# dm_in.net
KiCad netlist of a schematic drawn in EAGLE
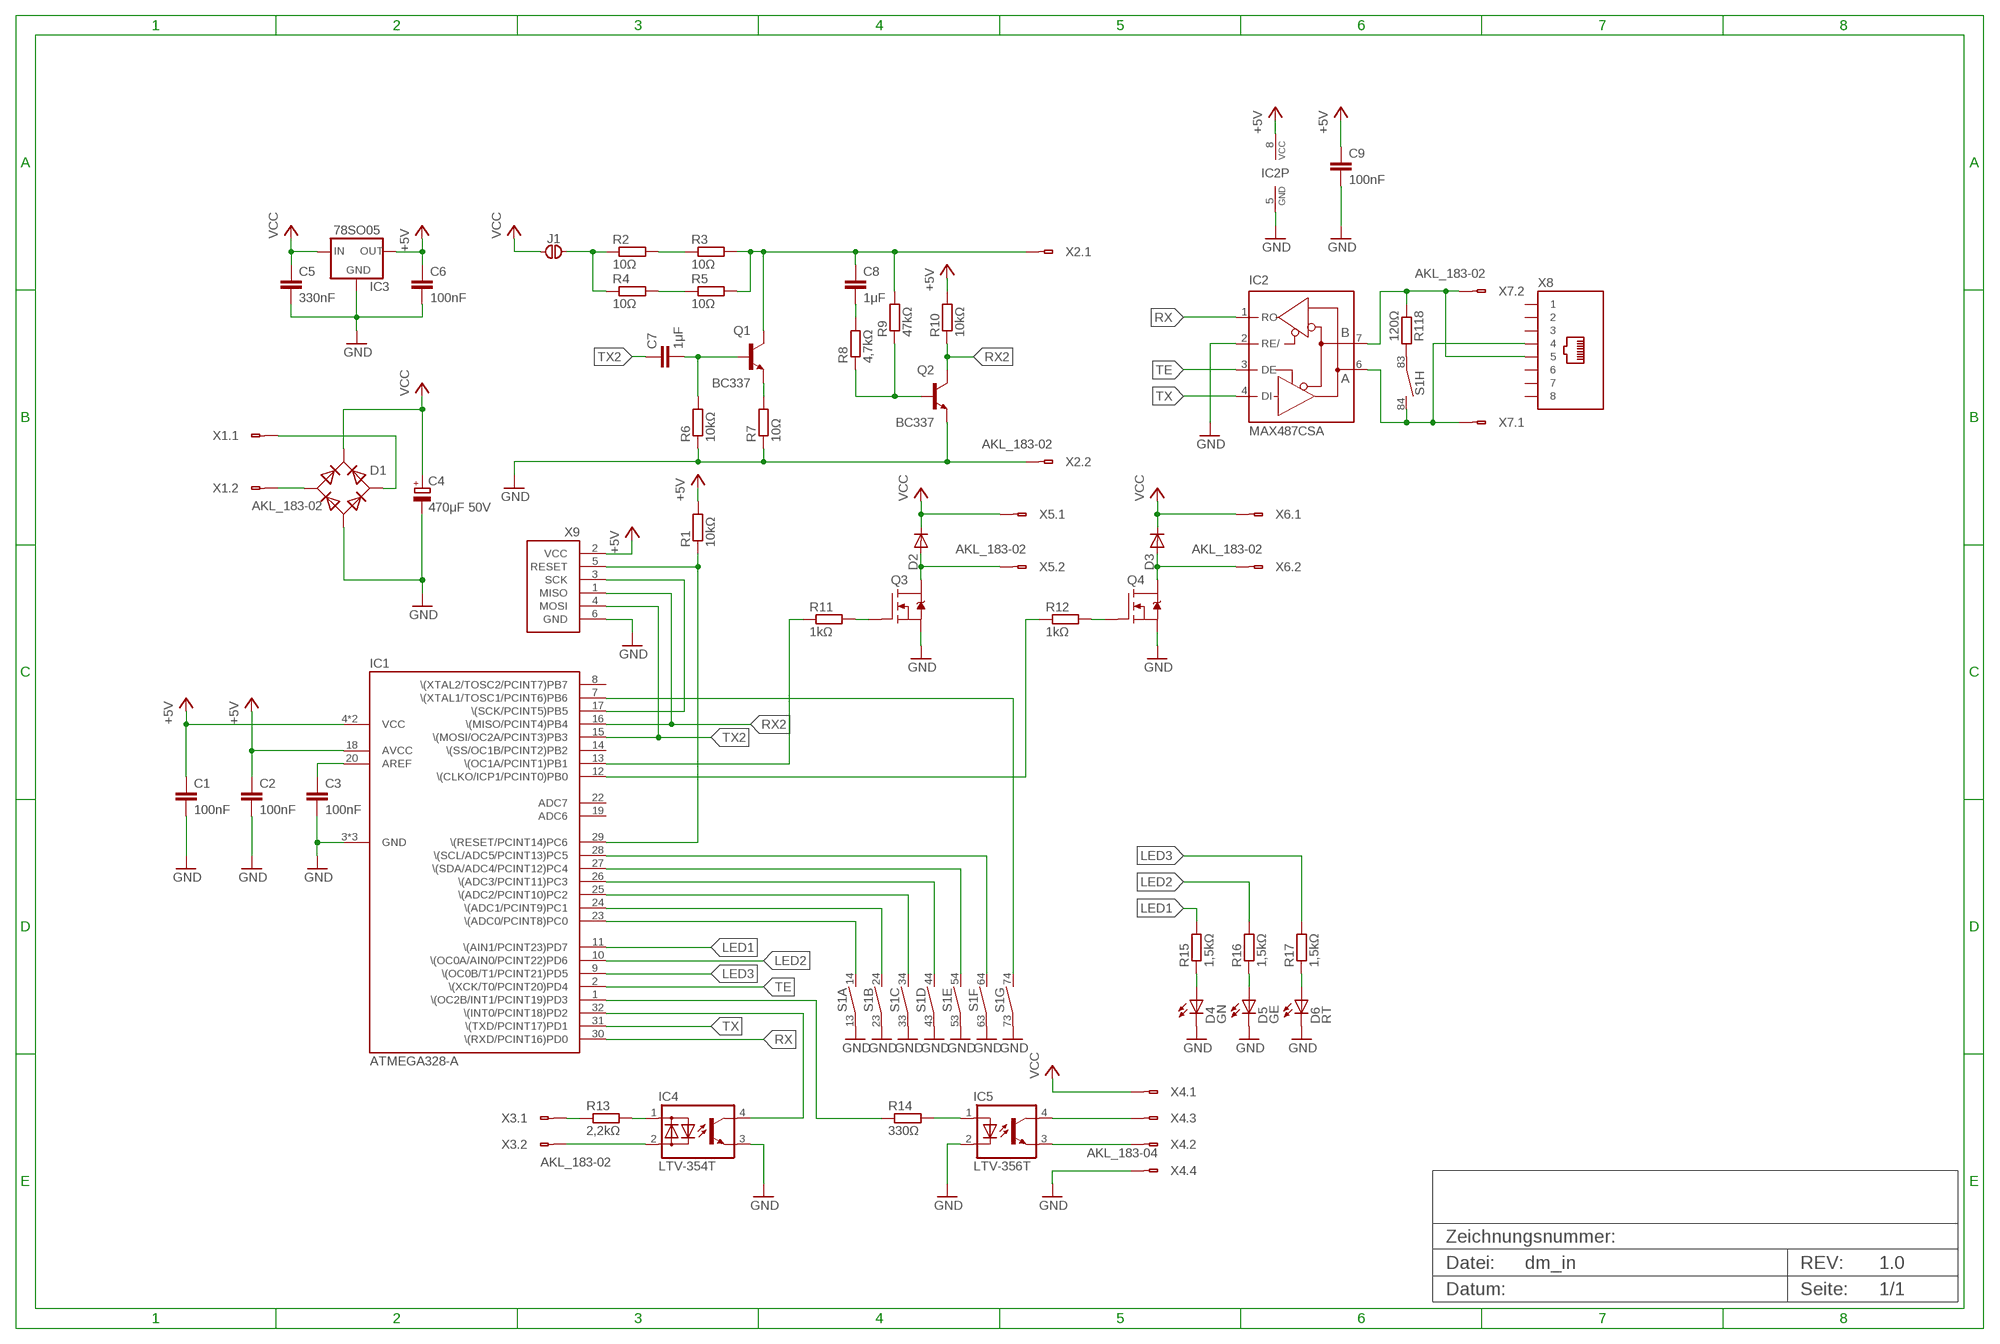
[diagram p0: schematic, sheet 1]

(export (version "E")
  (design (tool "Eeschema 10.0.6"))
  (components
    (comp (ref "C1")
      (value "100nF")
      (footprint "eagle-import:CHIP_0603")
      (libsource (lib "eagle-import") (part "C_0603"))
    )
    (comp (ref "C2")
      (value "100nF")
      (footprint "eagle-import:CHIP_0603")
      (libsource (lib "eagle-import") (part "C_0603"))
    )
    (comp (ref "C3")
      (value "100nF")
      (footprint "eagle-import:CHIP_0603")
      (libsource (lib "eagle-import") (part "C_0603"))
    )
    (comp (ref "C4")
      (value "470μF 50V")
      (footprint "eagle-import:E5-13")
      (libsource (lib "eagle-import") (part "C_EL_E5-13"))
    )
    (comp (ref "C5")
      (value "330nF")
      (footprint "eagle-import:CHIP_0805")
      (libsource (lib "eagle-import") (part "C_0805"))
    )
    (comp (ref "C6")
      (value "100nF")
      (footprint "eagle-import:CHIP_0805")
      (libsource (lib "eagle-import") (part "C_0805"))
    )
    (comp (ref "C7")
      (value "1μF")
      (footprint "eagle-import:CHIP_1206")
      (libsource (lib "eagle-import") (part "C_1206"))
    )
    (comp (ref "C8")
      (value "1μF")
      (footprint "eagle-import:CHIP_1206")
      (libsource (lib "eagle-import") (part "C_1206"))
    )
    (comp (ref "C9")
      (value "100nF")
      (footprint "eagle-import:CHIP_0603")
      (libsource (lib "eagle-import") (part "C_0603"))
    )
    (comp (ref "D1")
      (value "GLEICHRICHTER-SDIP")
      (footprint "eagle-import:SDIP04_508")
      (libsource (lib "eagle-import") (part "GLEICHRICHTER-SDIP"))
    )
    (comp (ref "D2")
      (value "DIODE-SOD123")
      (footprint "eagle-import:SOD123")
      (libsource (lib "eagle-import") (part "DIODE-SOD123"))
    )
    (comp (ref "D3")
      (value "DIODE-SOD123")
      (footprint "eagle-import:SOD123")
      (libsource (lib "eagle-import") (part "DIODE-SOD123"))
    )
    (comp (ref "D4")
      (value "GN")
      (footprint "eagle-import:CHIP_0805")
      (libsource (lib "eagle-import") (part "LED_0805"))
    )
    (comp (ref "D5")
      (value "GE")
      (footprint "eagle-import:CHIP_0805")
      (libsource (lib "eagle-import") (part "LED_0805"))
    )
    (comp (ref "D6")
      (value "RT")
      (footprint "eagle-import:CHIP_0805")
      (libsource (lib "eagle-import") (part "LED_0805"))
    )
    (comp (ref "IC1")
      (value "ATMEGA328-A")
      (footprint "eagle-import:QFP32_08")
      (libsource (lib "eagle-import") (part "ATMEGA328-A"))
    )
    (comp (ref "IC2")
      (value "MAX487CSA")
      (footprint "eagle-import:SOP08_127")
      (libsource (lib "eagle-import") (part "MAX48CSA7"))
    )
    (comp (ref "IC3")
      (value "78SO05")
      (footprint "eagle-import:SOP08_127")
      (libsource (lib "eagle-import") (part "78?SO05"))
    )
    (comp (ref "IC4")
      (value "LTV-354T")
      (footprint "eagle-import:SOP04_254")
      (libsource (lib "eagle-import") (part "LTV-354T"))
    )
    (comp (ref "IC5")
      (value "LTV-356T")
      (footprint "eagle-import:SOP04_254")
      (libsource (lib "eagle-import") (part "LTV-356T"))
    )
    (comp (ref "J1")
      (value "JUMPER")
      (footprint "eagle-import:JUMPER2")
      (libsource (lib "eagle-import") (part "JUMPER"))
    )
    (comp (ref "Q1")
      (value "BC337")
      (footprint "eagle-import:SOT23")
      (libsource (lib "eagle-import") (part "NPN-SOT23-BEC"))
    )
    (comp (ref "Q2")
      (value "BC337")
      (footprint "eagle-import:SOT23")
      (libsource (lib "eagle-import") (part "NPN-SOT23-BEC"))
    )
    (comp (ref "Q3")
      (value "N-MOS-SOT23-GSD")
      (footprint "eagle-import:SOT23")
      (libsource (lib "eagle-import") (part "N-MOS-SOT23-GSD"))
    )
    (comp (ref "Q4")
      (value "N-MOS-SOT23-GSD")
      (footprint "eagle-import:SOT23")
      (libsource (lib "eagle-import") (part "N-MOS-SOT23-GSD"))
    )
    (comp (ref "R1")
      (value "10kΩ")
      (footprint "eagle-import:CHIP_0603")
      (libsource (lib "eagle-import") (part "R_0603"))
    )
    (comp (ref "R2")
      (value "10Ω")
      (footprint "eagle-import:CHIP_1206")
      (libsource (lib "eagle-import") (part "R_1206"))
    )
    (comp (ref "R3")
      (value "10Ω")
      (footprint "eagle-import:CHIP_1206")
      (libsource (lib "eagle-import") (part "R_1206"))
    )
    (comp (ref "R4")
      (value "10Ω")
      (footprint "eagle-import:CHIP_1206")
      (libsource (lib "eagle-import") (part "R_1206"))
    )
    (comp (ref "R5")
      (value "10Ω")
      (footprint "eagle-import:CHIP_1206")
      (libsource (lib "eagle-import") (part "R_1206"))
    )
    (comp (ref "R6")
      (value "10kΩ")
      (footprint "eagle-import:CHIP_0603")
      (libsource (lib "eagle-import") (part "R_0603"))
    )
    (comp (ref "R7")
      (value "10Ω")
      (footprint "eagle-import:CHIP_1206")
      (libsource (lib "eagle-import") (part "R_1206"))
    )
    (comp (ref "R8")
      (value "4,7kΩ")
      (footprint "eagle-import:CHIP_0603")
      (libsource (lib "eagle-import") (part "R_0603"))
    )
    (comp (ref "R9")
      (value "47kΩ")
      (footprint "eagle-import:CHIP_0603")
      (libsource (lib "eagle-import") (part "R_0603"))
    )
    (comp (ref "R10")
      (value "10kΩ")
      (footprint "eagle-import:CHIP_0603")
      (libsource (lib "eagle-import") (part "R_0603"))
    )
    (comp (ref "R11")
      (value "1kΩ")
      (footprint "eagle-import:CHIP_0603")
      (libsource (lib "eagle-import") (part "R_0603"))
    )
    (comp (ref "R12")
      (value "1kΩ")
      (footprint "eagle-import:CHIP_0603")
      (libsource (lib "eagle-import") (part "R_0603"))
    )
    (comp (ref "R13")
      (value "2,2kΩ")
      (footprint "eagle-import:CHIP_0603")
      (libsource (lib "eagle-import") (part "R_0603"))
    )
    (comp (ref "R14")
      (value "330Ω")
      (footprint "eagle-import:CHIP_0603")
      (libsource (lib "eagle-import") (part "R_0603"))
    )
    (comp (ref "R15")
      (value "1,5kΩ")
      (footprint "eagle-import:CHIP_0603")
      (libsource (lib "eagle-import") (part "R_0603"))
    )
    (comp (ref "R16")
      (value "1,5kΩ")
      (footprint "eagle-import:CHIP_0603")
      (libsource (lib "eagle-import") (part "R_0603"))
    )
    (comp (ref "R17")
      (value "1,5kΩ")
      (footprint "eagle-import:CHIP_0603")
      (libsource (lib "eagle-import") (part "R_0603"))
    )
    (comp (ref "R118")
      (value "120Ω")
      (footprint "eagle-import:CHIP_0805")
      (libsource (lib "eagle-import") (part "R_0805"))
    )
    (comp (ref "S1")
      (value "DP08D")
      (footprint "eagle-import:DIP08_SMD")
      (libsource (lib "eagle-import") (part "DP08D"))
    )
    (comp (ref "X1")
      (value "AKL_183-02")
      (footprint "eagle-import:AKL_183-02")
      (libsource (lib "eagle-import") (part "AKL_183-02"))
    )
    (comp (ref "X2")
      (value "AKL_183-02")
      (footprint "eagle-import:AKL_183-02")
      (libsource (lib "eagle-import") (part "AKL_183-02"))
    )
    (comp (ref "X3")
      (value "AKL_183-02")
      (footprint "eagle-import:AKL_183-02")
      (libsource (lib "eagle-import") (part "AKL_183-02"))
    )
    (comp (ref "X4")
      (value "AKL_183-04")
      (footprint "eagle-import:AKL_183-04")
      (libsource (lib "eagle-import") (part "AKL_183-04"))
    )
    (comp (ref "X5")
      (value "AKL_183-02")
      (footprint "eagle-import:AKL_183-02")
      (libsource (lib "eagle-import") (part "AKL_183-02"))
    )
    (comp (ref "X6")
      (value "AKL_183-02")
      (footprint "eagle-import:AKL_183-02")
      (libsource (lib "eagle-import") (part "AKL_183-02"))
    )
    (comp (ref "X7")
      (value "AKL_183-02")
      (footprint "eagle-import:AKL_183-02")
      (libsource (lib "eagle-import") (part "AKL_183-02"))
    )
    (comp (ref "X8")
      (value "8P8C")
      (footprint "eagle-import:C-BMJ-0102")
      (libsource (lib "eagle-import") (part "8P8C"))
    )
    (comp (ref "X9")
      (value "ISP-AVR6")
      (footprint "eagle-import:ML6")
      (libsource (lib "eagle-import") (part "ISP-AVR6"))
    )
  )
  (nets
    (net (code "1") (name "+5V") (class "Default")
      (node (ref "C1") (pin "1") (pinfunction "1_1") (pintype "passive"))
      (node (ref "C2") (pin "1") (pinfunction "1_1") (pintype "passive"))
      (node (ref "C6") (pin "1") (pinfunction "1_1") (pintype "passive"))
      (node (ref "C9") (pin "1") (pinfunction "1_1") (pintype "passive"))
      (node (ref "IC1") (pin "18") (pinfunction "AVCC_18") (pintype "power_in"))
      (node (ref "IC1") (pin "4") (pinfunction "VCC_4") (pintype "power_in"))
      (node (ref "IC1") (pin "6") (pinfunction "VCC_6") (pintype "power_in"))
      (node (ref "IC2") (pin "8") (pinfunction "VCC_8") (pintype "power_in"))
      (node (ref "IC3") (pin "1") (pinfunction "OUT_1") (pintype "passive"))
      (node (ref "R1") (pin "2") (pinfunction "2_2") (pintype "passive"))
      (node (ref "R10") (pin "2") (pinfunction "2_2") (pintype "passive"))
      (node (ref "X9") (pin "2") (pinfunction "VCC_2") (pintype "power_in"))
    )
    (net (code "2") (name "GND") (class "Default")
      (node (ref "C1") (pin "2") (pinfunction "2_2") (pintype "passive"))
      (node (ref "C2") (pin "2") (pinfunction "2_2") (pintype "passive"))
      (node (ref "C3") (pin "2") (pinfunction "2_2") (pintype "passive"))
      (node (ref "C4") (pin "-") (pinfunction "-_-") (pintype "passive"))
      (node (ref "C5") (pin "2") (pinfunction "2_2") (pintype "passive"))
      (node (ref "C6") (pin "2") (pinfunction "2_2") (pintype "passive"))
      (node (ref "C9") (pin "2") (pinfunction "2_2") (pintype "passive"))
      (node (ref "D1") (pin "2") (pinfunction "-_2") (pintype "passive"))
      (node (ref "D4") (pin "2") (pinfunction "C_2") (pintype "passive"))
      (node (ref "D5") (pin "2") (pinfunction "C_2") (pintype "passive"))
      (node (ref "D6") (pin "2") (pinfunction "C_2") (pintype "passive"))
      (node (ref "IC1") (pin "21") (pinfunction "GND_21") (pintype "power_in"))
      (node (ref "IC1") (pin "3") (pinfunction "GND_3") (pintype "power_in"))
      (node (ref "IC1") (pin "5") (pinfunction "GND_5") (pintype "power_in"))
      (node (ref "IC2") (pin "2") (pinfunction "RE/_2") (pintype "input"))
      (node (ref "IC2") (pin "5") (pinfunction "GND_5") (pintype "power_in"))
      (node (ref "IC3") (pin "2") (pinfunction "GND_2") (pintype "input"))
      (node (ref "IC3") (pin "3") (pinfunction "GND_3") (pintype "input"))
      (node (ref "IC3") (pin "6") (pinfunction "GND_6") (pintype "input"))
      (node (ref "IC3") (pin "7") (pinfunction "GND_7") (pintype "input"))
      (node (ref "IC4") (pin "3") (pinfunction "E_3") (pintype "passive"))
      (node (ref "IC5") (pin "2") (pinfunction "K_2") (pintype "passive"))
      (node (ref "Q2") (pin "2") (pinfunction "E_2") (pintype "passive"))
      (node (ref "Q3") (pin "2") (pinfunction "S_2") (pintype "passive"))
      (node (ref "Q4") (pin "2") (pinfunction "S_2") (pintype "passive"))
      (node (ref "R6") (pin "1") (pinfunction "1_1") (pintype "passive"))
      (node (ref "R7") (pin "1") (pinfunction "1_1") (pintype "passive"))
      (node (ref "S1") (pin "13") (pinfunction "3_13") (pintype "passive"))
      (node (ref "S1") (pin "23") (pinfunction "3_23") (pintype "passive"))
      (node (ref "S1") (pin "33") (pinfunction "3_33") (pintype "passive"))
      (node (ref "S1") (pin "43") (pinfunction "3_43") (pintype "passive"))
      (node (ref "S1") (pin "53") (pinfunction "3_53") (pintype "passive"))
      (node (ref "S1") (pin "63") (pinfunction "3_63") (pintype "passive"))
      (node (ref "S1") (pin "73") (pinfunction "3_73") (pintype "passive"))
      (node (ref "X2") (pin "2") (pinfunction "A_2") (pintype "passive"))
      (node (ref "X4") (pin "4") (pinfunction "A_4") (pintype "passive"))
      (node (ref "X9") (pin "6") (pinfunction "GND_6") (pintype "power_in"))
    )
    (net (code "3") (name "LED1") (class "Default")
      (node (ref "IC1") (pin "11") (pinfunction "\\(AIN1/PCINT23)PD7_11") (pintype "bidirectional"))
      (node (ref "R15") (pin "2") (pinfunction "2_2") (pintype "passive"))
    )
    (net (code "4") (name "LED2") (class "Default")
      (node (ref "IC1") (pin "10") (pinfunction "\\(OC0A/AIN0/PCINT22)PD6_10") (pintype "bidirectional"))
      (node (ref "R16") (pin "2") (pinfunction "2_2") (pintype "passive"))
    )
    (net (code "5") (name "LED3") (class "Default")
      (node (ref "IC1") (pin "9") (pinfunction "\\(OC0B/T1/PCINT21)PD5_9") (pintype "bidirectional"))
      (node (ref "R17") (pin "2") (pinfunction "2_2") (pintype "passive"))
    )
    (net (code "6") (name "Net-(C8-Pad2)") (class "Default")
      (node (ref "C8") (pin "2") (pinfunction "2_2") (pintype "passive"))
      (node (ref "R8") (pin "2") (pinfunction "2_2") (pintype "passive"))
    )
    (net (code "7") (name "Net-(D1-AC1)") (class "Default")
      (node (ref "D1") (pin "3") (pinfunction "AC1_3") (pintype "passive"))
      (node (ref "X1") (pin "2") (pinfunction "A_2") (pintype "passive"))
    )
    (net (code "8") (name "Net-(D1-AC2)") (class "Default")
      (node (ref "D1") (pin "4") (pinfunction "AC2_4") (pintype "passive"))
      (node (ref "X1") (pin "1") (pinfunction "A_1") (pintype "passive"))
    )
    (net (code "9") (name "Net-(D4-A)") (class "Default")
      (node (ref "D4") (pin "1") (pinfunction "A_1") (pintype "passive"))
      (node (ref "R15") (pin "1") (pinfunction "1_1") (pintype "passive"))
    )
    (net (code "10") (name "Net-(D5-A)") (class "Default")
      (node (ref "D5") (pin "1") (pinfunction "A_1") (pintype "passive"))
      (node (ref "R16") (pin "1") (pinfunction "1_1") (pintype "passive"))
    )
    (net (code "11") (name "Net-(D6-A)") (class "Default")
      (node (ref "D6") (pin "1") (pinfunction "A_1") (pintype "passive"))
      (node (ref "R17") (pin "1") (pinfunction "1_1") (pintype "passive"))
    )
    (net (code "12") (name "Net-(IC1-AREF)") (class "Default")
      (node (ref "C3") (pin "1") (pinfunction "1_1") (pintype "passive"))
      (node (ref "IC1") (pin "20") (pinfunction "AREF_20") (pintype "passive"))
    )
    (net (code "13") (name "Net-(IC1-\\(ADC0{slash}PCINT8)PC0)") (class "Default")
      (node (ref "IC1") (pin "23") (pinfunction "\\(ADC0/PCINT8)PC0_23") (pintype "bidirectional"))
      (node (ref "S1") (pin "14") (pinfunction "4_14") (pintype "passive"))
    )
    (net (code "14") (name "Net-(IC1-\\(ADC1{slash}PCINT9)PC1)") (class "Default")
      (node (ref "IC1") (pin "24") (pinfunction "\\(ADC1/PCINT9)PC1_24") (pintype "bidirectional"))
      (node (ref "S1") (pin "24") (pinfunction "4_24") (pintype "passive"))
    )
    (net (code "15") (name "Net-(IC1-\\(ADC2{slash}PCINT10)PC2)") (class "Default")
      (node (ref "IC1") (pin "25") (pinfunction "\\(ADC2/PCINT10)PC2_25") (pintype "bidirectional"))
      (node (ref "S1") (pin "34") (pinfunction "4_34") (pintype "passive"))
    )
    (net (code "16") (name "Net-(IC1-\\(ADC3{slash}PCINT11)PC3)") (class "Default")
      (node (ref "IC1") (pin "26") (pinfunction "\\(ADC3/PCINT11)PC3_26") (pintype "bidirectional"))
      (node (ref "S1") (pin "44") (pinfunction "4_44") (pintype "passive"))
    )
    (net (code "17") (name "Net-(IC1-\\(CLKO{slash}ICP1{slash}PCINT0)PB0)") (class "Default")
      (node (ref "IC1") (pin "12") (pinfunction "\\(CLKO/ICP1/PCINT0)PB0_12") (pintype "bidirectional"))
      (node (ref "R12") (pin "1") (pinfunction "1_1") (pintype "passive"))
    )
    (net (code "18") (name "Net-(IC1-\\(INT0{slash}PCINT18)PD2)") (class "Default")
      (node (ref "IC1") (pin "32") (pinfunction "\\(INT0/PCINT18)PD2_32") (pintype "bidirectional"))
      (node (ref "IC4") (pin "4") (pinfunction "C_4") (pintype "passive"))
    )
    (net (code "19") (name "Net-(IC1-\\(OC1A{slash}PCINT1)PB1)") (class "Default")
      (node (ref "IC1") (pin "13") (pinfunction "\\(OC1A/PCINT1)PB1_13") (pintype "bidirectional"))
      (node (ref "R11") (pin "1") (pinfunction "1_1") (pintype "passive"))
    )
    (net (code "20") (name "Net-(IC1-\\(OC2B{slash}INT1{slash}PCINT19)PD3)") (class "Default")
      (node (ref "IC1") (pin "1") (pinfunction "\\(OC2B/INT1/PCINT19)PD3_1") (pintype "bidirectional"))
      (node (ref "R14") (pin "1") (pinfunction "1_1") (pintype "passive"))
    )
    (net (code "21") (name "Net-(IC1-\\(RESET{slash}PCINT14)PC6)") (class "Default")
      (node (ref "IC1") (pin "29") (pinfunction "\\(RESET/PCINT14)PC6_29") (pintype "bidirectional"))
      (node (ref "R1") (pin "1") (pinfunction "1_1") (pintype "passive"))
      (node (ref "X9") (pin "5") (pinfunction "RESET_5") (pintype "passive"))
    )
    (net (code "22") (name "Net-(IC1-\\(SCK{slash}PCINT5)PB5)") (class "Default")
      (node (ref "IC1") (pin "17") (pinfunction "\\(SCK/PCINT5)PB5_17") (pintype "bidirectional"))
      (node (ref "X9") (pin "3") (pinfunction "SCK_3") (pintype "passive"))
    )
    (net (code "23") (name "Net-(IC1-\\(SCL{slash}ADC5{slash}PCINT13)PC5)") (class "Default")
      (node (ref "IC1") (pin "28") (pinfunction "\\(SCL/ADC5/PCINT13)PC5_28") (pintype "bidirectional"))
      (node (ref "S1") (pin "64") (pinfunction "4_64") (pintype "passive"))
    )
    (net (code "24") (name "Net-(IC1-\\(SDA{slash}ADC4{slash}PCINT12)PC4)") (class "Default")
      (node (ref "IC1") (pin "27") (pinfunction "\\(SDA/ADC4/PCINT12)PC4_27") (pintype "bidirectional"))
      (node (ref "S1") (pin "54") (pinfunction "4_54") (pintype "passive"))
    )
    (net (code "25") (name "Net-(IC1-\\(XTAL1{slash}TOSC1{slash}PCINT6)PB6)") (class "Default")
      (node (ref "IC1") (pin "7") (pinfunction "\\(XTAL1/TOSC1/PCINT6)PB6_7") (pintype "bidirectional"))
      (node (ref "S1") (pin "74") (pinfunction "4_74") (pintype "passive"))
    )
    (net (code "26") (name "Net-(IC2A-A)") (class "Default")
      (node (ref "IC2") (pin "6") (pinfunction "A_6") (pintype "passive"))
      (node (ref "S1") (pin "84") (pinfunction "4_84") (pintype "passive"))
      (node (ref "X7") (pin "1") (pinfunction "A_1") (pintype "passive"))
      (node (ref "X8") (pin "P$4") (pinfunction "4_P$4") (pintype "passive"))
    )
    (net (code "27") (name "Net-(IC2A-B)") (class "Default")
      (node (ref "IC2") (pin "7") (pinfunction "B_7") (pintype "passive"))
      (node (ref "R118") (pin "1") (pinfunction "1_1") (pintype "passive"))
      (node (ref "X7") (pin "2") (pinfunction "A_2") (pintype "passive"))
      (node (ref "X8") (pin "P$5") (pinfunction "5_P$5") (pintype "passive"))
    )
    (net (code "28") (name "Net-(IC4-A)") (class "Default")
      (node (ref "IC4") (pin "1") (pinfunction "A_1") (pintype "passive"))
      (node (ref "R13") (pin "2") (pinfunction "2_2") (pintype "passive"))
    )
    (net (code "29") (name "Net-(IC4-K)") (class "Default")
      (node (ref "IC4") (pin "2") (pinfunction "K_2") (pintype "passive"))
      (node (ref "X3") (pin "2") (pinfunction "A_2") (pintype "passive"))
    )
    (net (code "30") (name "Net-(IC5-A)") (class "Default")
      (node (ref "IC5") (pin "1") (pinfunction "A_1") (pintype "passive"))
      (node (ref "R14") (pin "2") (pinfunction "2_2") (pintype "passive"))
    )
    (net (code "31") (name "Net-(IC5-C)") (class "Default")
      (node (ref "IC5") (pin "4") (pinfunction "C_4") (pintype "passive"))
      (node (ref "X4") (pin "3") (pinfunction "A_3") (pintype "passive"))
    )
    (net (code "32") (name "Net-(IC5-E)") (class "Default")
      (node (ref "IC5") (pin "3") (pinfunction "E_3") (pintype "passive"))
      (node (ref "X4") (pin "2") (pinfunction "A_2") (pintype "passive"))
    )
    (net (code "33") (name "Net-(J1-PadP$2)") (class "Default")
      (node (ref "J1") (pin "P$2") (pinfunction "P$2_P$2") (pintype "passive"))
      (node (ref "R2") (pin "1") (pinfunction "1_1") (pintype "passive"))
      (node (ref "R4") (pin "1") (pinfunction "1_1") (pintype "passive"))
    )
    (net (code "34") (name "Net-(Q1-B)") (class "Default")
      (node (ref "C7") (pin "2") (pinfunction "2_2") (pintype "passive"))
      (node (ref "Q1") (pin "1") (pinfunction "B_1") (pintype "passive"))
      (node (ref "R6") (pin "2") (pinfunction "2_2") (pintype "passive"))
    )
    (net (code "35") (name "Net-(Q1-C)") (class "Default")
      (node (ref "C8") (pin "1") (pinfunction "1_1") (pintype "passive"))
      (node (ref "Q1") (pin "3") (pinfunction "C_3") (pintype "passive"))
      (node (ref "R3") (pin "2") (pinfunction "2_2") (pintype "passive"))
      (node (ref "R5") (pin "2") (pinfunction "2_2") (pintype "passive"))
      (node (ref "R9") (pin "2") (pinfunction "2_2") (pintype "passive"))
      (node (ref "X2") (pin "1") (pinfunction "A_1") (pintype "passive"))
    )
    (net (code "36") (name "Net-(Q1-E)") (class "Default")
      (node (ref "Q1") (pin "2") (pinfunction "E_2") (pintype "passive"))
      (node (ref "R7") (pin "2") (pinfunction "2_2") (pintype "passive"))
    )
    (net (code "37") (name "Net-(Q2-B)") (class "Default")
      (node (ref "Q2") (pin "1") (pinfunction "B_1") (pintype "passive"))
      (node (ref "R8") (pin "1") (pinfunction "1_1") (pintype "passive"))
      (node (ref "R9") (pin "1") (pinfunction "1_1") (pintype "passive"))
    )
    (net (code "38") (name "Net-(Q3-D)") (class "Default")
      (node (ref "D2") (pin "A") (pinfunction "A_A") (pintype "passive"))
      (node (ref "Q3") (pin "3") (pinfunction "D_3") (pintype "passive"))
      (node (ref "X5") (pin "2") (pinfunction "A_2") (pintype "passive"))
    )
    (net (code "39") (name "Net-(Q3-G)") (class "Default")
      (node (ref "Q3") (pin "1") (pinfunction "G_1") (pintype "passive"))
      (node (ref "R11") (pin "2") (pinfunction "2_2") (pintype "passive"))
    )
    (net (code "40") (name "Net-(Q4-D)") (class "Default")
      (node (ref "D3") (pin "A") (pinfunction "A_A") (pintype "passive"))
      (node (ref "Q4") (pin "3") (pinfunction "D_3") (pintype "passive"))
      (node (ref "X6") (pin "2") (pinfunction "A_2") (pintype "passive"))
    )
    (net (code "41") (name "Net-(Q4-G)") (class "Default")
      (node (ref "Q4") (pin "1") (pinfunction "G_1") (pintype "passive"))
      (node (ref "R12") (pin "2") (pinfunction "2_2") (pintype "passive"))
    )
    (net (code "42") (name "Net-(R2-Pad2)") (class "Default")
      (node (ref "R2") (pin "2") (pinfunction "2_2") (pintype "passive"))
      (node (ref "R3") (pin "1") (pinfunction "1_1") (pintype "passive"))
    )
    (net (code "43") (name "Net-(R4-Pad2)") (class "Default")
      (node (ref "R4") (pin "2") (pinfunction "2_2") (pintype "passive"))
      (node (ref "R5") (pin "1") (pinfunction "1_1") (pintype "passive"))
    )
    (net (code "44") (name "Net-(S1H-3)") (class "Default")
      (node (ref "R118") (pin "2") (pinfunction "2_2") (pintype "passive"))
      (node (ref "S1") (pin "83") (pinfunction "3_83") (pintype "passive"))
    )
    (net (code "45") (name "Net-(X3A-A)") (class "Default")
      (node (ref "R13") (pin "1") (pinfunction "1_1") (pintype "passive"))
      (node (ref "X3") (pin "1") (pinfunction "A_1") (pintype "passive"))
    )
    (net (code "46") (name "RX") (class "Default")
      (node (ref "IC1") (pin "30") (pinfunction "\\(RXD/PCINT16)PD0_30") (pintype "bidirectional"))
      (node (ref "IC2") (pin "1") (pinfunction "RO_1") (pintype "output"))
    )
    (net (code "47") (name "RX2") (class "Default")
      (node (ref "IC1") (pin "16") (pinfunction "\\(MISO/PCINT4)PB4_16") (pintype "bidirectional"))
      (node (ref "Q2") (pin "3") (pinfunction "C_3") (pintype "passive"))
      (node (ref "R10") (pin "1") (pinfunction "1_1") (pintype "passive"))
      (node (ref "X9") (pin "1") (pinfunction "MISO_1") (pintype "passive"))
    )
    (net (code "48") (name "TE") (class "Default")
      (node (ref "IC1") (pin "2") (pinfunction "\\(XCK/T0/PCINT20)PD4_2") (pintype "bidirectional"))
      (node (ref "IC2") (pin "3") (pinfunction "DE_3") (pintype "input"))
    )
    (net (code "49") (name "TX") (class "Default")
      (node (ref "IC1") (pin "31") (pinfunction "\\(TXD/PCINT17)PD1_31") (pintype "bidirectional"))
      (node (ref "IC2") (pin "4") (pinfunction "DI_4") (pintype "input"))
    )
    (net (code "50") (name "TX2") (class "Default")
      (node (ref "C7") (pin "1") (pinfunction "1_1") (pintype "passive"))
      (node (ref "IC1") (pin "15") (pinfunction "\\(MOSI/OC2A/PCINT3)PB3_15") (pintype "bidirectional"))
      (node (ref "X9") (pin "4") (pinfunction "MOSI_4") (pintype "passive"))
    )
    (net (code "51") (name "VCC") (class "Default")
      (node (ref "C4") (pin "+") (pinfunction "+_+") (pintype "passive"))
      (node (ref "C5") (pin "1") (pinfunction "1_1") (pintype "passive"))
      (node (ref "D1") (pin "1") (pinfunction "+_1") (pintype "passive"))
      (node (ref "D2") (pin "K") (pinfunction "K_K") (pintype "passive"))
      (node (ref "D3") (pin "K") (pinfunction "K_K") (pintype "passive"))
      (node (ref "IC3") (pin "8") (pinfunction "IN_8") (pintype "input"))
      (node (ref "J1") (pin "P$1") (pinfunction "P$1_P$1") (pintype "passive"))
      (node (ref "X4") (pin "1") (pinfunction "A_1") (pintype "passive"))
      (node (ref "X5") (pin "1") (pinfunction "A_1") (pintype "passive"))
      (node (ref "X6") (pin "1") (pinfunction "A_1") (pintype "passive"))
    )
    (net (code "52") (name "unconnected-(IC1-ADC6-Pad19)") (class "Default")
      (node (ref "IC1") (pin "19") (pinfunction "ADC6_19") (pintype "bidirectional"))
    )
    (net (code "53") (name "unconnected-(IC1-ADC7-Pad22)") (class "Default")
      (node (ref "IC1") (pin "22") (pinfunction "ADC7_22") (pintype "bidirectional"))
    )
    (net (code "54") (name "unconnected-(IC1-\\(SS{slash}OC1B{slash}PCINT2)PB2-Pad14)") (class "Default")
      (node (ref "IC1") (pin "14") (pinfunction "\\(SS/OC1B/PCINT2)PB2_14") (pintype "bidirectional"))
    )
    (net (code "55") (name "unconnected-(IC1-\\(XTAL2{slash}TOSC2{slash}PCINT7)PB7-Pad8)") (class "Default")
      (node (ref "IC1") (pin "8") (pinfunction "\\(XTAL2/TOSC2/PCINT7)PB7_8") (pintype "bidirectional"))
    )
    (net (code "56") (name "unconnected-(X8-1-PadP$1)") (class "Default")
      (node (ref "X8") (pin "P$1") (pinfunction "1_P$1") (pintype "passive"))
    )
    (net (code "57") (name "unconnected-(X8-2-PadP$2)") (class "Default")
      (node (ref "X8") (pin "P$2") (pinfunction "2_P$2") (pintype "passive"))
    )
    (net (code "58") (name "unconnected-(X8-3-PadP$3)") (class "Default")
      (node (ref "X8") (pin "P$3") (pinfunction "3_P$3") (pintype "passive"))
    )
    (net (code "59") (name "unconnected-(X8-6-PadP$6)") (class "Default")
      (node (ref "X8") (pin "P$6") (pinfunction "6_P$6") (pintype "passive"))
    )
    (net (code "60") (name "unconnected-(X8-7-PadP$7)") (class "Default")
      (node (ref "X8") (pin "P$7") (pinfunction "7_P$7") (pintype "passive"))
    )
    (net (code "61") (name "unconnected-(X8-8-PadP$8)") (class "Default")
      (node (ref "X8") (pin "P$8") (pinfunction "8_P$8") (pintype "passive"))
    )
  )
)
